# Schematic_Drohne.net
KiCad netlist of a schematic drawn in Altium Designer
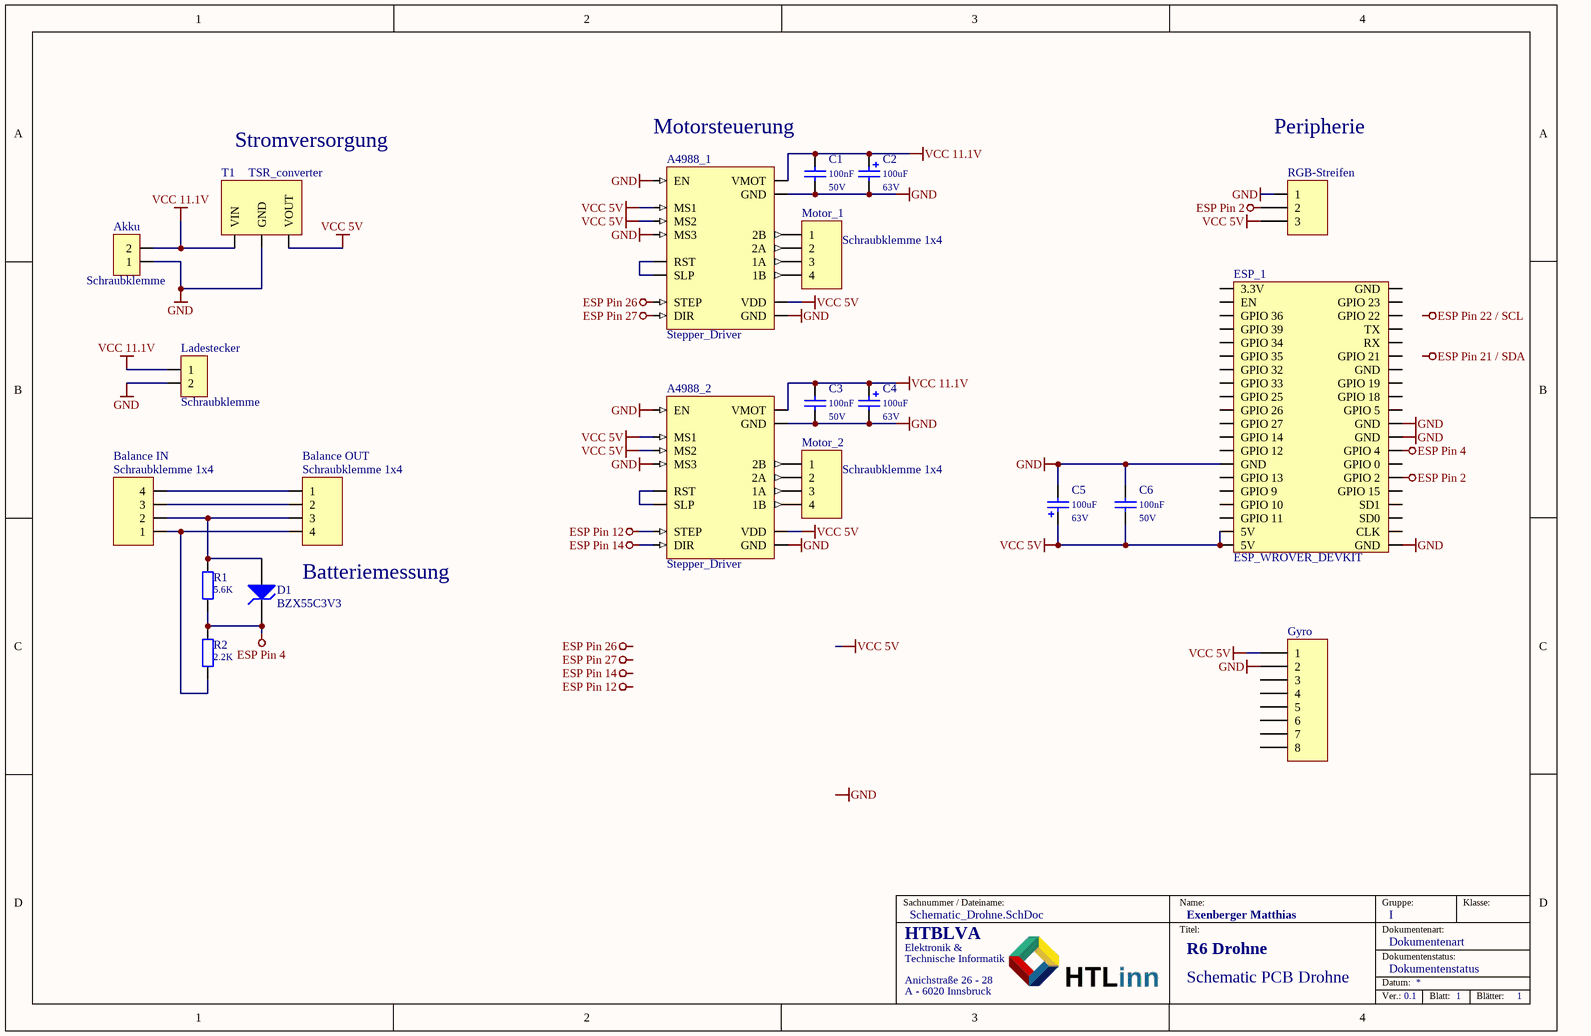
[diagram p0: Schematic_Drohne.SchDoc]

(export (version "E")
  (design (tool "Eeschema 10.0.6"))
  (components
    (comp (ref "A4988_1")
      (value "Stepper_Driver")
      (footprint "A4988")
      (libsource (lib "A4988") (part "Stepper_Driver"))
    )
    (comp (ref "A4988_2")
      (value "Stepper_Driver")
      (footprint "A4988")
      (libsource (lib "A4988") (part "Stepper_Driver"))
    )
    (comp (ref "Akku")
      (value "Schraubklemme")
      (footprint "Schraubklemme_1x2")
      (libsource (lib "Schraubklemme_1x2") (part "Schraubklemme_1x2"))
    )
    (comp (ref "Balance IN")
      (value "Schraubklemme 1x4")
      (footprint "CTB0502-4")
      (libsource (lib "") (part "Schraubklemme 1x4_1"))
    )
    (comp (ref "Balance OUT")
      (value "Schraubklemme 1x4")
      (footprint "CTB0502-4")
      (libsource (lib "Schraubklemme_1x4") (part "Schraubklemme 1x4"))
    )
    (comp (ref "C1")
      (value "100nF")
      (footprint "C_RM2-025X075 - with Ceramic Disc Capacitor")
      (description "Capacitor")
      (fields (field (name "RATED VOLTAGE") "50V"))
      (libsource (lib "HTLInn_RLCQ") (part "C"))
    )
    (comp (ref "C2")
      (value "100uF")
      (footprint "C_POL_RM2-10,5 x 12.5mm")
      (description "Polarized Capacitor")
      (fields (field (name "RATED VOLTAGE") "63V"))
      (libsource (lib "HTLInn_RLCQ") (part "C_POL"))
    )
    (comp (ref "C3")
      (value "100nF")
      (footprint "C_RM2-025X075 - with Ceramic Disc Capacitor")
      (description "Capacitor")
      (fields (field (name "RATED VOLTAGE") "50V"))
      (libsource (lib "HTLInn_RLCQ") (part "C"))
    )
    (comp (ref "C4")
      (value "100uF")
      (footprint "C_POL_RM2-10,5 x 12.5mm")
      (description "Polarized Capacitor")
      (fields (field (name "RATED VOLTAGE") "63V"))
      (libsource (lib "HTLInn_RLCQ") (part "C_POL"))
    )
    (comp (ref "C5")
      (value "100uF")
      (footprint "C_POL_RM2-10,5 x 12.5mm")
      (description "Polarized Capacitor")
      (fields (field (name "RATED VOLTAGE") "63V"))
      (libsource (lib "HTLInn_RLCQ") (part "C_POL"))
    )
    (comp (ref "C6")
      (value "100nF")
      (footprint "C_RM2-025X075 - with Ceramic Disc Capacitor")
      (description "Capacitor")
      (fields (field (name "RATED VOLTAGE") "50V"))
      (libsource (lib "HTLInn_RLCQ") (part "C"))
    )
    (comp (ref "D1")
      (value "BZX55C3V3")
      (footprint "D_DO35-RM3")
      (description "Zener Diode 3.3V, 500mW (Silicon Epitaxial Planar)")
      (fields (field (name "PUBLISHER") "Michael Kupfner"))
      (libsource (lib "HTLinn_D") (part "BZX55C3V3"))
    )
    (comp (ref "ESP_1")
      (value "ESP_WROVER_DEVKIT")
      (footprint "ESP_WROVER_DEVKIT")
      (libsource (lib "ESP_WROVER_MODULE") (part "ESP_WROVER_DEVKIT"))
    )
    (comp (ref "Gyro")
      (value "Header 8")
      (footprint "HDR1X8")
      (description "Header, 8-Pin")
      (fields (field (name "PUBLISHER") "Altium Limited"))
      (libsource (lib "Miscellaneous Connectors") (part "Header 8"))
    )
    (comp (ref "Ladestecker")
      (value "Schraubklemme")
      (footprint "Schraubklemme_1x2")
      (libsource (lib "") (part "Schraubklemme_1x2_1"))
    )
    (comp (ref "Motor_1")
      (value "Schraubklemme 1x4")
      (footprint "CTB0502-4")
      (libsource (lib "Schraubklemme_1x4") (part "Schraubklemme 1x4"))
    )
    (comp (ref "Motor_2")
      (value "Schraubklemme 1x4")
      (footprint "CTB0502-4")
      (libsource (lib "Schraubklemme_1x4") (part "Schraubklemme 1x4"))
    )
    (comp (ref "R1")
      (value "5.6K")
      (footprint "R_0204V/RM1 - 1k")
      (description "Resistor")
      (libsource (lib "HTLInn_RLCQ") (part "R"))
    )
    (comp (ref "R2")
      (value "2.2K")
      (footprint "R_0204V/RM1 - 1k")
      (description "Resistor")
      (libsource (lib "HTLInn_RLCQ") (part "R"))
    )
    (comp (ref "RGB-Streifen")
      (value "~")
      (footprint "HDR1X3")
      (description "Header, 3-Pin")
      (fields (field (name "PUBLISHER") "Altium Limited"))
      (libsource (lib "Miscellaneous Connectors") (part "Header 3"))
    )
    (comp (ref "T1")
      (value "TSR_converter")
      (footprint "PCBComponent_1")
      (libsource (lib "TSR-0-5-2450") (part "TSR-0-5-2450"))
    )
  )
  (nets
    (net (code "1") (name "ESP Pin 2") (class "Default")
      (node (ref "ESP_1") (pin "35") (pinfunction "GPIO_2_35") (pintype "bidirectional"))
      (node (ref "RGB-Streifen") (pin "2") (pinfunction "2_2") (pintype "passive"))
    )
    (net (code "2") (name "ESP Pin 4") (class "Default")
      (node (ref "D1") (pin "2") (pinfunction "K_2") (pintype "passive"))
      (node (ref "ESP_1") (pin "33") (pinfunction "GPIO_4_33") (pintype "bidirectional"))
      (node (ref "R1") (pin "2") (pinfunction "2_2") (pintype "passive"))
      (node (ref "R2") (pin "1") (pinfunction "1_1") (pintype "passive"))
    )
    (net (code "3") (name "ESP Pin 12") (class "Default")
      (node (ref "A4988_2") (pin "7") (pinfunction "STEP_7") (pintype "input"))
    )
    (net (code "4") (name "ESP Pin 14") (class "Default")
      (node (ref "A4988_2") (pin "8") (pinfunction "DIR_8") (pintype "input"))
    )
    (net (code "7") (name "ESP Pin 26") (class "Default")
      (node (ref "A4988_1") (pin "7") (pinfunction "STEP_7") (pintype "input"))
    )
    (net (code "8") (name "ESP Pin 27") (class "Default")
      (node (ref "A4988_1") (pin "8") (pinfunction "DIR_8") (pintype "input"))
    )
    (net (code "9") (name "GND") (class "Default")
      (node (ref "A4988_1") (pin "1") (pinfunction "EN_1") (pintype "input"))
      (node (ref "A4988_1") (pin "10") (pinfunction "GND_10") (pintype "power_in"))
      (node (ref "A4988_1") (pin "16") (pinfunction "GND_16") (pintype "power_in"))
      (node (ref "A4988_1") (pin "4") (pinfunction "MS3_4") (pintype "input"))
      (node (ref "A4988_2") (pin "1") (pinfunction "EN_1") (pintype "input"))
      (node (ref "A4988_2") (pin "10") (pinfunction "GND_10") (pintype "power_in"))
      (node (ref "A4988_2") (pin "16") (pinfunction "GND_16") (pintype "power_in"))
      (node (ref "A4988_2") (pin "4") (pinfunction "MS3_4") (pintype "input"))
      (node (ref "Akku") (pin "1") (pinfunction "1_1") (pintype "passive"))
      (node (ref "C1") (pin "1") (pinfunction "1_1") (pintype "passive"))
      (node (ref "C2") (pin "2") (pinfunction "-_2") (pintype "passive"))
      (node (ref "C3") (pin "1") (pinfunction "1_1") (pintype "passive"))
      (node (ref "C4") (pin "2") (pinfunction "-_2") (pintype "passive"))
      (node (ref "C5") (pin "2") (pinfunction "-_2") (pintype "passive"))
      (node (ref "C6") (pin "2") (pinfunction "2_2") (pintype "passive"))
      (node (ref "ESP_1") (pin "14") (pinfunction "GND_14") (pintype "power_in"))
      (node (ref "ESP_1") (pin "31") (pinfunction "GND_31") (pintype "power_in"))
      (node (ref "ESP_1") (pin "32") (pinfunction "GND_32") (pintype "power_in"))
      (node (ref "ESP_1") (pin "40") (pinfunction "GND_40") (pintype "power_in"))
      (node (ref "Gyro") (pin "2") (pinfunction "2_2") (pintype "passive"))
      (node (ref "Ladestecker") (pin "2") (pinfunction "2_2") (pintype "passive"))
      (node (ref "RGB-Streifen") (pin "1") (pinfunction "1_1") (pintype "passive"))
      (node (ref "T1") (pin "2") (pinfunction "GND_2") (pintype "passive"))
    )
    (net (code "10") (name "Net-(A4988_1-1A)") (class "Default")
      (node (ref "A4988_1") (pin "13") (pinfunction "1A_13") (pintype "output"))
      (node (ref "Motor_1") (pin "3") (pinfunction "3_3") (pintype "passive"))
    )
    (net (code "11") (name "Net-(A4988_1-1B)") (class "Default")
      (node (ref "A4988_1") (pin "14") (pinfunction "1B_14") (pintype "output"))
      (node (ref "Motor_1") (pin "4") (pinfunction "4_4") (pintype "passive"))
    )
    (net (code "12") (name "Net-(A4988_1-2A)") (class "Default")
      (node (ref "A4988_1") (pin "12") (pinfunction "2A_12") (pintype "output"))
      (node (ref "Motor_1") (pin "2") (pinfunction "2_2") (pintype "passive"))
    )
    (net (code "13") (name "Net-(A4988_1-2B)") (class "Default")
      (node (ref "A4988_1") (pin "11") (pinfunction "2B_11") (pintype "output"))
      (node (ref "Motor_1") (pin "1") (pinfunction "1_1") (pintype "passive"))
    )
    (net (code "14") (name "Net-(A4988_1-RST)") (class "Default")
      (node (ref "A4988_1") (pin "5") (pinfunction "RST_5") (pintype "passive"))
      (node (ref "A4988_1") (pin "6") (pinfunction "SLP_6") (pintype "passive"))
    )
    (net (code "15") (name "Net-(A4988_2-1A)") (class "Default")
      (node (ref "A4988_2") (pin "13") (pinfunction "1A_13") (pintype "output"))
      (node (ref "Motor_2") (pin "3") (pinfunction "3_3") (pintype "passive"))
    )
    (net (code "16") (name "Net-(A4988_2-1B)") (class "Default")
      (node (ref "A4988_2") (pin "14") (pinfunction "1B_14") (pintype "output"))
      (node (ref "Motor_2") (pin "4") (pinfunction "4_4") (pintype "passive"))
    )
    (net (code "17") (name "Net-(A4988_2-2A)") (class "Default")
      (node (ref "A4988_2") (pin "12") (pinfunction "2A_12") (pintype "output"))
      (node (ref "Motor_2") (pin "2") (pinfunction "2_2") (pintype "passive"))
    )
    (net (code "18") (name "Net-(A4988_2-2B)") (class "Default")
      (node (ref "A4988_2") (pin "11") (pinfunction "2B_11") (pintype "output"))
      (node (ref "Motor_2") (pin "1") (pinfunction "1_1") (pintype "passive"))
    )
    (net (code "19") (name "Net-(A4988_2-RST)") (class "Default")
      (node (ref "A4988_2") (pin "5") (pinfunction "RST_5") (pintype "passive"))
      (node (ref "A4988_2") (pin "6") (pinfunction "SLP_6") (pintype "passive"))
    )
    (net (code "20") (name "Net-(Balance IN-Pad1)") (class "Default")
      (node (ref "Balance IN") (pin "1") (pinfunction "1_1") (pintype "passive"))
      (node (ref "Balance OUT") (pin "4") (pinfunction "4_4") (pintype "passive"))
      (node (ref "R2") (pin "2") (pinfunction "2_2") (pintype "passive"))
    )
    (net (code "21") (name "Net-(Balance IN-Pad3)") (class "Default")
      (node (ref "Balance IN") (pin "3") (pinfunction "3_3") (pintype "passive"))
      (node (ref "Balance OUT") (pin "2") (pinfunction "2_2") (pintype "passive"))
    )
    (net (code "22") (name "Net-(Balance IN-Pad4)") (class "Default")
      (node (ref "Balance IN") (pin "4") (pinfunction "4_4") (pintype "passive"))
      (node (ref "Balance OUT") (pin "1") (pinfunction "1_1") (pintype "passive"))
    )
    (net (code "23") (name "Net-(D1-A)") (class "Default")
      (node (ref "Balance IN") (pin "2") (pinfunction "2_2") (pintype "passive"))
      (node (ref "Balance OUT") (pin "3") (pinfunction "3_3") (pintype "passive"))
      (node (ref "D1") (pin "1") (pinfunction "A_1") (pintype "passive"))
      (node (ref "R1") (pin "1") (pinfunction "1_1") (pintype "passive"))
    )
    (net (code "24") (name "VCC 5V") (class "Default")
      (node (ref "A4988_1") (pin "15") (pinfunction "VDD_15") (pintype "power_in"))
      (node (ref "A4988_1") (pin "2") (pinfunction "MS1_2") (pintype "input"))
      (node (ref "A4988_1") (pin "3") (pinfunction "MS2_3") (pintype "input"))
      (node (ref "A4988_2") (pin "15") (pinfunction "VDD_15") (pintype "power_in"))
      (node (ref "A4988_2") (pin "2") (pinfunction "MS1_2") (pintype "input"))
      (node (ref "A4988_2") (pin "3") (pinfunction "MS2_3") (pintype "input"))
      (node (ref "C5") (pin "1") (pinfunction "+_1") (pintype "passive"))
      (node (ref "C6") (pin "1") (pinfunction "1_1") (pintype "passive"))
      (node (ref "ESP_1") (pin "19") (pinfunction "5V_19") (pintype "power_in"))
      (node (ref "ESP_1") (pin "20") (pinfunction "5V_20") (pintype "power_in"))
      (node (ref "Gyro") (pin "1") (pinfunction "1_1") (pintype "passive"))
      (node (ref "RGB-Streifen") (pin "3") (pinfunction "3_3") (pintype "passive"))
      (node (ref "T1") (pin "3") (pinfunction "VOUT_3") (pintype "passive"))
    )
    (net (code "25") (name "VCC 11.1V") (class "Default")
      (node (ref "A4988_1") (pin "9") (pinfunction "VMOT_9") (pintype "power_in"))
      (node (ref "A4988_2") (pin "9") (pinfunction "VMOT_9") (pintype "power_in"))
      (node (ref "Akku") (pin "2") (pinfunction "2_2") (pintype "passive"))
      (node (ref "C1") (pin "2") (pinfunction "2_2") (pintype "passive"))
      (node (ref "C2") (pin "1") (pinfunction "+_1") (pintype "passive"))
      (node (ref "C3") (pin "2") (pinfunction "2_2") (pintype "passive"))
      (node (ref "C4") (pin "1") (pinfunction "+_1") (pintype "passive"))
      (node (ref "Ladestecker") (pin "1") (pinfunction "1_1") (pintype "passive"))
      (node (ref "T1") (pin "1") (pinfunction "VIN_1") (pintype "passive"))
    )
    (net (code "26") (name "unconnected-(ESP_1-3.3V-Pad1)") (class "Default")
      (node (ref "ESP_1") (pin "1") (pinfunction "3.3V_1") (pintype "power_in"))
    )
    (net (code "27") (name "unconnected-(ESP_1-CLK-Pad39)") (class "Default")
      (node (ref "ESP_1") (pin "39") (pinfunction "CLK_39") (pintype "bidirectional"))
    )
    (net (code "28") (name "unconnected-(ESP_1-EN-Pad2)") (class "Default")
      (node (ref "ESP_1") (pin "2") (pinfunction "EN_2") (pintype "passive"))
    )
    (net (code "29") (name "unconnected-(ESP_1-GND-Pad21)") (class "Default")
      (node (ref "ESP_1") (pin "21") (pinfunction "GND_21") (pintype "power_in"))
    )
    (net (code "30") (name "unconnected-(ESP_1-GND-Pad27)") (class "Default")
      (node (ref "ESP_1") (pin "27") (pinfunction "GND_27") (pintype "power_in"))
    )
    (net (code "31") (name "unconnected-(ESP_1-GPIO_0-Pad34)") (class "Default")
      (node (ref "ESP_1") (pin "34") (pinfunction "GPIO_0_34") (pintype "bidirectional"))
    )
    (net (code "32") (name "unconnected-(ESP_1-GPIO_5-Pad30)") (class "Default")
      (node (ref "ESP_1") (pin "30") (pinfunction "GPIO_5_30") (pintype "bidirectional"))
    )
    (net (code "33") (name "unconnected-(ESP_1-GPIO_9-Pad16)") (class "Default")
      (node (ref "ESP_1") (pin "16") (pinfunction "GPIO_9_16") (pintype "bidirectional"))
    )
    (net (code "34") (name "unconnected-(ESP_1-GPIO_10-Pad17)") (class "Default")
      (node (ref "ESP_1") (pin "17") (pinfunction "GPIO_10_17") (pintype "bidirectional"))
    )
    (net (code "35") (name "unconnected-(ESP_1-GPIO_11-Pad18)") (class "Default")
      (node (ref "ESP_1") (pin "18") (pinfunction "GPIO_11_18") (pintype "bidirectional"))
    )
    (net (code "36") (name "unconnected-(ESP_1-GPIO_12-Pad13)") (class "Default")
      (node (ref "ESP_1") (pin "13") (pinfunction "GPIO_12_13") (pintype "bidirectional"))
    )
    (net (code "37") (name "unconnected-(ESP_1-GPIO_13-Pad15)") (class "Default")
      (node (ref "ESP_1") (pin "15") (pinfunction "GPIO_13_15") (pintype "bidirectional"))
    )
    (net (code "38") (name "unconnected-(ESP_1-GPIO_14-Pad12)") (class "Default")
      (node (ref "ESP_1") (pin "12") (pinfunction "GPIO_14_12") (pintype "bidirectional"))
    )
    (net (code "39") (name "unconnected-(ESP_1-GPIO_15-Pad36)") (class "Default")
      (node (ref "ESP_1") (pin "36") (pinfunction "GPIO_15_36") (pintype "bidirectional"))
    )
    (net (code "40") (name "unconnected-(ESP_1-GPIO_18-Pad29)") (class "Default")
      (node (ref "ESP_1") (pin "29") (pinfunction "GPIO_18_29") (pintype "bidirectional"))
    )
    (net (code "41") (name "unconnected-(ESP_1-GPIO_19-Pad28)") (class "Default")
      (node (ref "ESP_1") (pin "28") (pinfunction "GPIO_19_28") (pintype "bidirectional"))
    )
    (net (code "42") (name "unconnected-(ESP_1-GPIO_21-Pad26)") (class "Default")
      (node (ref "ESP_1") (pin "26") (pinfunction "GPIO_21_26") (pintype "bidirectional"))
    )
    (net (code "43") (name "unconnected-(ESP_1-GPIO_22-Pad23)") (class "Default")
      (node (ref "ESP_1") (pin "23") (pinfunction "GPIO_22_23") (pintype "bidirectional"))
    )
    (net (code "44") (name "unconnected-(ESP_1-GPIO_23-Pad22)") (class "Default")
      (node (ref "ESP_1") (pin "22") (pinfunction "GPIO_23_22") (pintype "bidirectional"))
    )
    (net (code "45") (name "unconnected-(ESP_1-GPIO_25-Pad9)") (class "Default")
      (node (ref "ESP_1") (pin "9") (pinfunction "GPIO_25_9") (pintype "bidirectional"))
    )
    (net (code "46") (name "unconnected-(ESP_1-GPIO_26-Pad10)") (class "Default")
      (node (ref "ESP_1") (pin "10") (pinfunction "GPIO_26_10") (pintype "bidirectional"))
    )
    (net (code "47") (name "unconnected-(ESP_1-GPIO_27-Pad11)") (class "Default")
      (node (ref "ESP_1") (pin "11") (pinfunction "GPIO_27_11") (pintype "bidirectional"))
    )
    (net (code "48") (name "unconnected-(ESP_1-GPIO_32-Pad7)") (class "Default")
      (node (ref "ESP_1") (pin "7") (pinfunction "GPIO_32_7") (pintype "bidirectional"))
    )
    (net (code "49") (name "unconnected-(ESP_1-GPIO_33-Pad8)") (class "Default")
      (node (ref "ESP_1") (pin "8") (pinfunction "GPIO_33_8") (pintype "bidirectional"))
    )
    (net (code "50") (name "unconnected-(ESP_1-GPIO_34-Pad5)") (class "Default")
      (node (ref "ESP_1") (pin "5") (pinfunction "GPIO_34_5") (pintype "bidirectional"))
    )
    (net (code "51") (name "unconnected-(ESP_1-GPIO_35-Pad6)") (class "Default")
      (node (ref "ESP_1") (pin "6") (pinfunction "GPIO_35_6") (pintype "bidirectional"))
    )
    (net (code "52") (name "unconnected-(ESP_1-GPIO_36-Pad3)") (class "Default")
      (node (ref "ESP_1") (pin "3") (pinfunction "GPIO_36_3") (pintype "bidirectional"))
    )
    (net (code "53") (name "unconnected-(ESP_1-GPIO_39-Pad4)") (class "Default")
      (node (ref "ESP_1") (pin "4") (pinfunction "GPIO_39_4") (pintype "bidirectional"))
    )
    (net (code "54") (name "unconnected-(ESP_1-RX-Pad25)") (class "Default")
      (node (ref "ESP_1") (pin "25") (pinfunction "RX_25") (pintype "bidirectional"))
    )
    (net (code "55") (name "unconnected-(ESP_1-SD0-Pad38)") (class "Default")
      (node (ref "ESP_1") (pin "38") (pinfunction "SD0_38") (pintype "bidirectional"))
    )
    (net (code "56") (name "unconnected-(ESP_1-SD1-Pad37)") (class "Default")
      (node (ref "ESP_1") (pin "37") (pinfunction "SD1_37") (pintype "bidirectional"))
    )
    (net (code "57") (name "unconnected-(ESP_1-TX-Pad24)") (class "Default")
      (node (ref "ESP_1") (pin "24") (pinfunction "TX_24") (pintype "bidirectional"))
    )
    (net (code "58") (name "unconnected-(Gyro-Pad3)") (class "Default")
      (node (ref "Gyro") (pin "3") (pinfunction "3_3") (pintype "passive"))
    )
    (net (code "59") (name "unconnected-(Gyro-Pad4)") (class "Default")
      (node (ref "Gyro") (pin "4") (pinfunction "4_4") (pintype "passive"))
    )
    (net (code "60") (name "unconnected-(Gyro-Pad5)") (class "Default")
      (node (ref "Gyro") (pin "5") (pinfunction "5_5") (pintype "passive"))
    )
    (net (code "61") (name "unconnected-(Gyro-Pad6)") (class "Default")
      (node (ref "Gyro") (pin "6") (pinfunction "6_6") (pintype "passive"))
    )
    (net (code "62") (name "unconnected-(Gyro-Pad7)") (class "Default")
      (node (ref "Gyro") (pin "7") (pinfunction "7_7") (pintype "passive"))
    )
    (net (code "63") (name "unconnected-(Gyro-Pad8)") (class "Default")
      (node (ref "Gyro") (pin "8") (pinfunction "8_8") (pintype "passive"))
    )
  )
)
